# FM-Radio-Simple-Receiver-BB.net
KiCad netlist of a schematic drawn in EAGLE
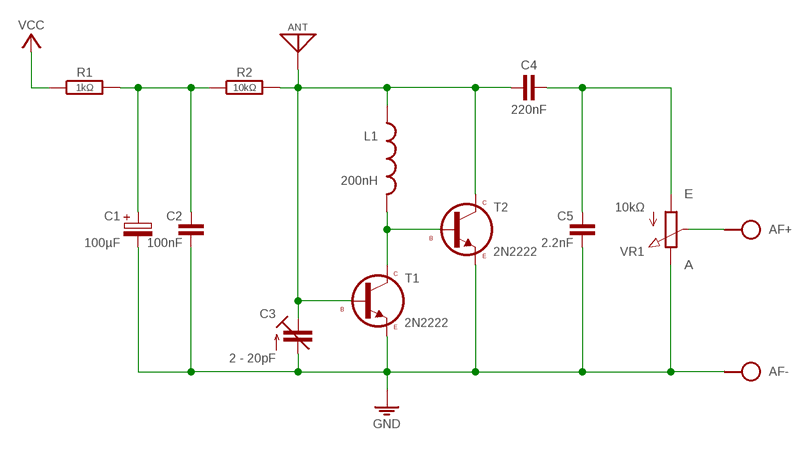
[diagram p0: schematic, sheet 1]

(export (version "E")
  (design (tool "Eeschema 10.0.6"))
  (components
    (comp (ref "AF")
      (value "SPAD+-+-")
      (footprint "eagle-import:SPAD+-")
      (libsource (lib "eagle-import") (part "SPAD+-+-"))
    )
    (comp (ref "ANT")
      (value "ANT")
      (footprint "eagle-import:SPAD")
      (libsource (lib "eagle-import") (part "ANT"))
    )
    (comp (ref "BAT")
      (value "VCC_GNDL")
      (footprint "eagle-import:SPAD-+")
      (libsource (lib "eagle-import") (part "VCC_GNDL"))
    )
    (comp (ref "C1")
      (value "100µF")
      (footprint "eagle-import:E2,5-5_V")
      (libsource (lib "eagle-import") (part "CPOLE2,5-5/V"))
    )
    (comp (ref "C2")
      (value "100nF")
      (footprint "eagle-import:C025-024X044")
      (libsource (lib "eagle-import") (part "C025-024X044"))
    )
    (comp (ref "C3")
      (value "2 - 20pF")
      (footprint "eagle-import:TRIM-2222-808")
      (libsource (lib "eagle-import") (part "C-TR-PH201272222-808-2PIND"))
    )
    (comp (ref "C4")
      (value "220nF")
      (footprint "eagle-import:C050-020X044")
      (libsource (lib "eagle-import") (part "C-H050-020X044"))
    )
    (comp (ref "C5")
      (value "2.2nF")
      (footprint "eagle-import:C050-020X036_V")
      (libsource (lib "eagle-import") (part "C050-020X036/V"))
    )
    (comp (ref "L1")
      (value "200nH")
      (footprint "eagle-import:L-04_8")
      (libsource (lib "eagle-import") (part "L04/08"))
    )
    (comp (ref "R1")
      (value "1kΩ")
      (footprint "eagle-import:0202_7-V")
      (libsource (lib "eagle-import") (part "R-H0202/7-V"))
    )
    (comp (ref "R2")
      (value "10kΩ")
      (footprint "eagle-import:0204_10-V")
      (libsource (lib "eagle-import") (part "R-H0204/10-V"))
    )
    (comp (ref "T1")
      (value "2N2222")
      (footprint "eagle-import:TO92")
      (libsource (lib "eagle-import") (part "2N2222"))
    )
    (comp (ref "T2")
      (value "2N2222")
      (footprint "eagle-import:TO92")
      (libsource (lib "eagle-import") (part "2N2222"))
    )
    (comp (ref "VR1")
      (value "10kΩ")
      (footprint "eagle-import:CONN-3P")
      (libsource (lib "eagle-import") (part "POT-3P"))
    )
  )
  (nets
    (net (code "1") (name "Net-(AFA-P$1)") (class "Default")
      (node (ref "AF") (pin "2") (pinfunction "P$1_2") (pintype "passive"))
      (node (ref "VR1") (pin "2") (pinfunction "S_2") (pintype "passive"))
    )
    (net (code "2") (name "Net-(AFB-P$1)") (class "Default")
      (node (ref "AF") (pin "1") (pinfunction "P$1_1") (pintype "passive"))
      (node (ref "BAT") (pin "1") (pinfunction "GND_1") (pintype "power_in"))
      (node (ref "C1") (pin "-") (pinfunction "-_-") (pintype "passive"))
      (node (ref "C2") (pin "2") (pinfunction "2_2") (pintype "passive"))
      (node (ref "C3") (pin "2") (pinfunction "A_2") (pintype "passive"))
      (node (ref "C5") (pin "2") (pinfunction "2_2") (pintype "passive"))
      (node (ref "T1") (pin "1") (pinfunction "E_1") (pintype "passive"))
      (node (ref "T2") (pin "1") (pinfunction "E_1") (pintype "passive"))
      (node (ref "VR1") (pin "3") (pinfunction "E_3") (pintype "passive"))
    )
    (net (code "3") (name "Net-(BATA-VCC)") (class "Default")
      (node (ref "BAT") (pin "2") (pinfunction "VCC_2") (pintype "power_in"))
      (node (ref "R1") (pin "1") (pinfunction "1_1") (pintype "passive"))
    )
    (net (code "4") (name "Net-(C1-Pad+)") (class "Default")
      (node (ref "C1") (pin "+") (pinfunction "+_+") (pintype "passive"))
      (node (ref "C2") (pin "1") (pinfunction "1_1") (pintype "passive"))
      (node (ref "R1") (pin "2") (pinfunction "2_2") (pintype "passive"))
      (node (ref "R2") (pin "1") (pinfunction "1_1") (pintype "passive"))
    )
    (net (code "5") (name "Net-(C3-E)") (class "Default")
      (node (ref "ANT") (pin "1") (pinfunction "1_1") (pintype "output"))
      (node (ref "C3") (pin "3") (pinfunction "E_3") (pintype "passive"))
      (node (ref "C4") (pin "1") (pinfunction "1_1") (pintype "passive"))
      (node (ref "L1") (pin "1") (pinfunction "1_1") (pintype "passive"))
      (node (ref "R2") (pin "2") (pinfunction "2_2") (pintype "passive"))
      (node (ref "T1") (pin "2") (pinfunction "B_2") (pintype "passive"))
      (node (ref "T2") (pin "3") (pinfunction "C_3") (pintype "passive"))
    )
    (net (code "6") (name "Net-(T1-C)") (class "Default")
      (node (ref "L1") (pin "2") (pinfunction "2_2") (pintype "passive"))
      (node (ref "T1") (pin "3") (pinfunction "C_3") (pintype "passive"))
      (node (ref "T2") (pin "2") (pinfunction "B_2") (pintype "passive"))
    )
    (net (code "7") (name "Net-(VR1-A)") (class "Default")
      (node (ref "C4") (pin "2") (pinfunction "2_2") (pintype "passive"))
      (node (ref "C5") (pin "1") (pinfunction "1_1") (pintype "passive"))
      (node (ref "VR1") (pin "1") (pinfunction "A_1") (pintype "passive"))
    )
  )
)
